# eCog100_ESP8266_Wifi.net
KiCad netlist of a schematic drawn in EAGLE
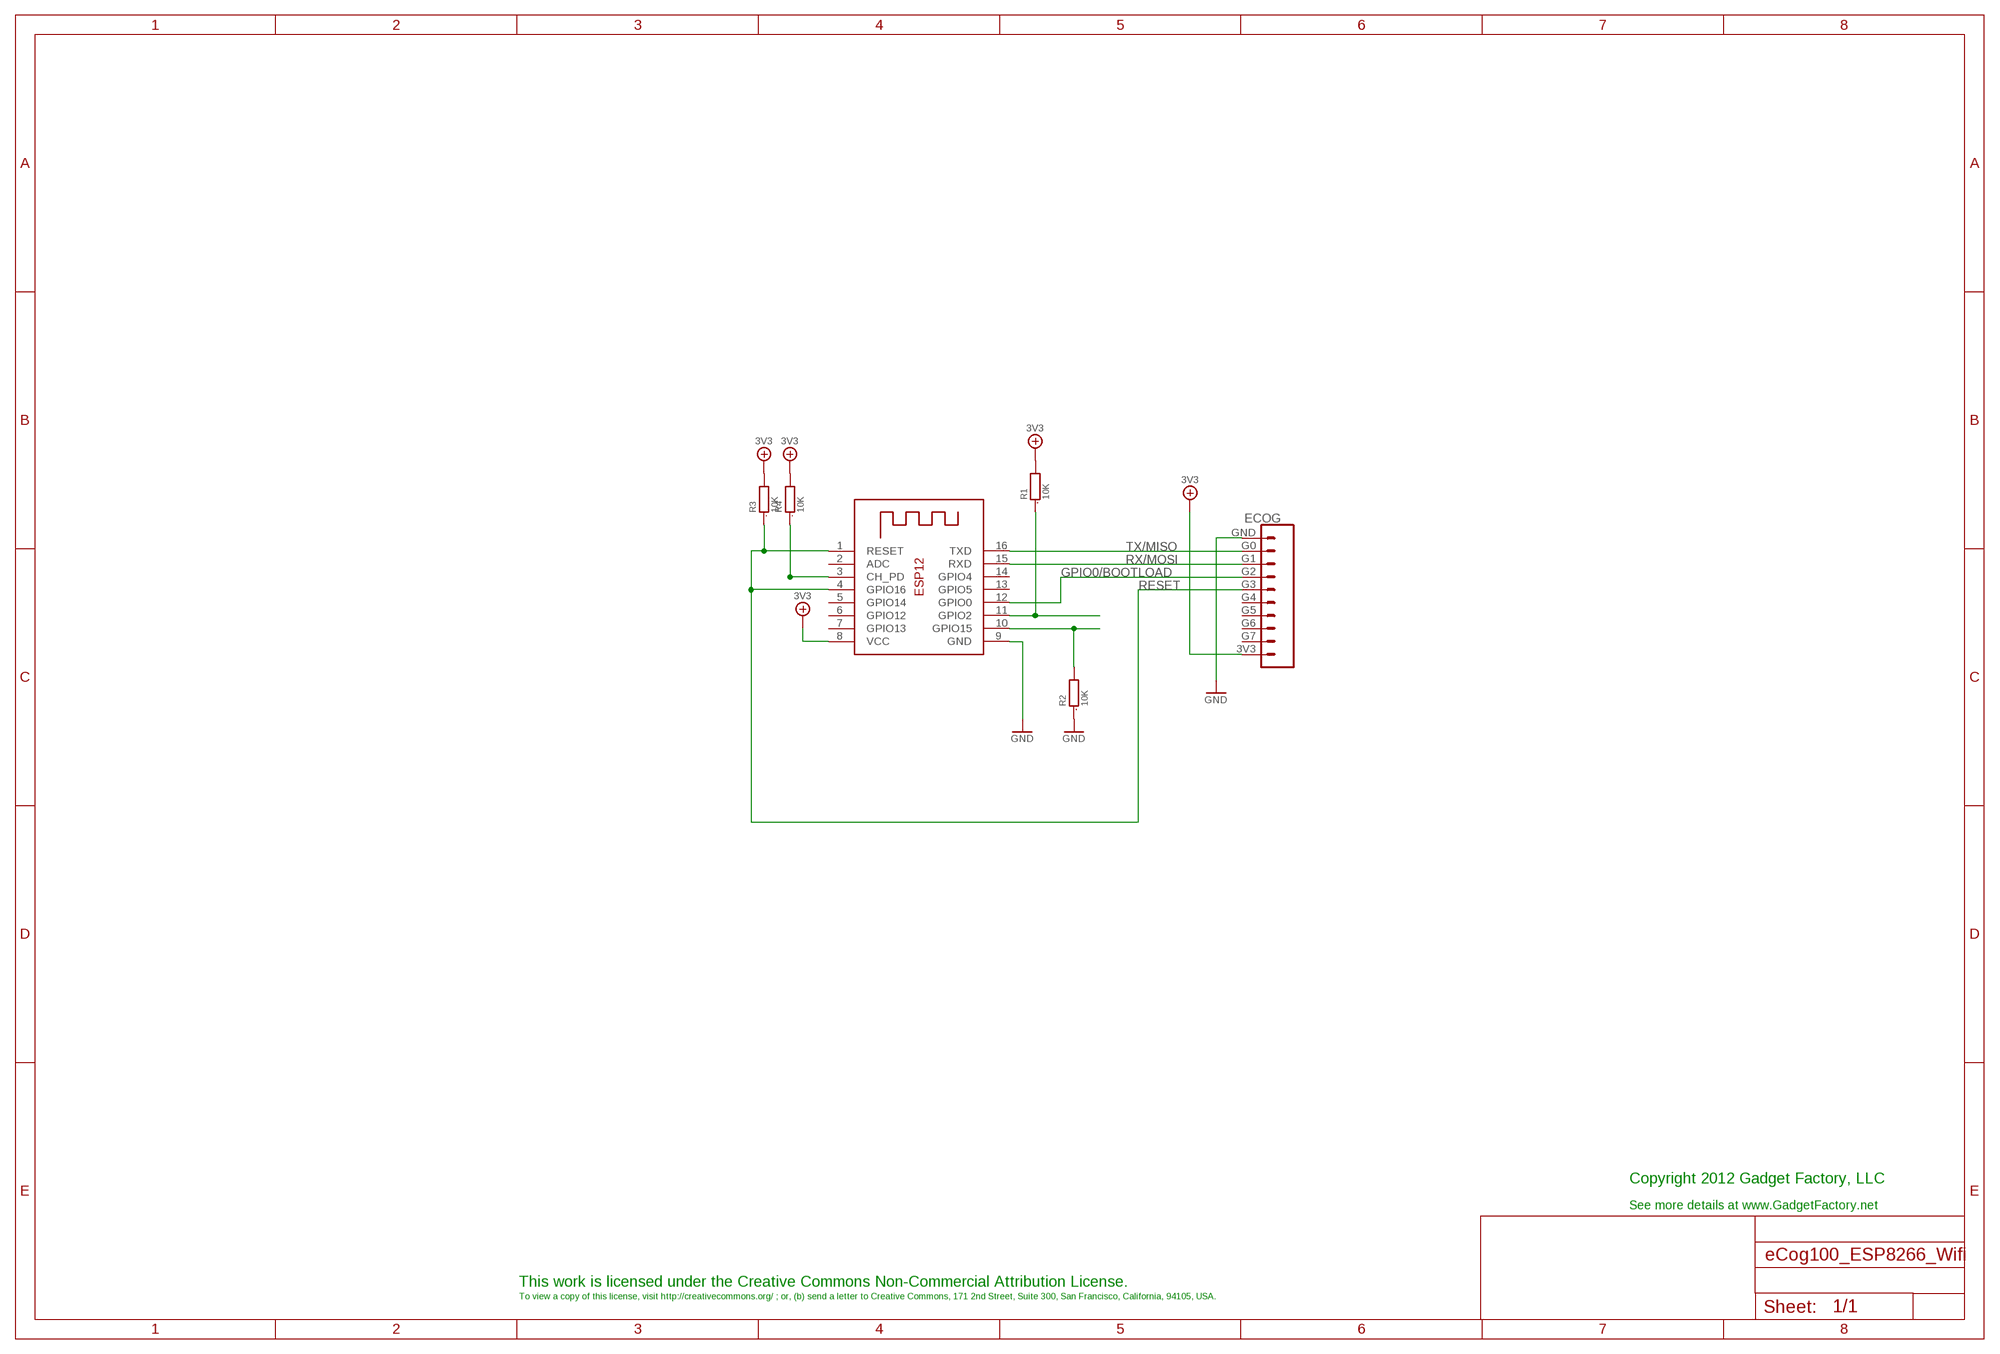
[diagram p0: schematic, sheet 1]

(export (version "E")
  (design (tool "Eeschema 10.0.6"))
  (components
    (comp (ref "ECOG")
      (value "ECOG_GENERAL_ROWSURFACEMOUNT")
      (footprint "eagle-import:ECOG_GENERAL_SMD")
      (libsource (lib "eagle-import") (part "ECOG_GENERAL_ROWSURFACEMOUNT"))
    )
    (comp (ref "R1")
      (value "10K")
      (footprint "eagle-import:0805")
      (libsource (lib "eagle-import") (part "R0805"))
    )
    (comp (ref "R2")
      (value "10K")
      (footprint "eagle-import:0805")
      (libsource (lib "eagle-import") (part "R0805"))
    )
    (comp (ref "R3")
      (value "10K")
      (footprint "eagle-import:0805")
      (libsource (lib "eagle-import") (part "R0805"))
    )
    (comp (ref "R4")
      (value "10K")
      (footprint "eagle-import:0805")
      (libsource (lib "eagle-import") (part "R0805"))
    )
    (comp (ref "X1")
      (value "ESP-12")
      (footprint "eagle-import:ESP-12")
      (libsource (lib "eagle-import") (part "ESP-12"))
    )
  )
  (nets
    (net (code "1") (name "/GPIO0{slash}BOOTLOAD") (class "Default")
      (node (ref "ECOG") (pin "G2") (pinfunction "G2_G2") (pintype "passive"))
      (node (ref "X1") (pin "12") (pinfunction "GPIO0_12") (pintype "bidirectional"))
    )
    (net (code "2") (name "/RESET") (class "Default")
      (node (ref "ECOG") (pin "G3") (pinfunction "G3_G3") (pintype "passive"))
      (node (ref "R3") (pin "1") (pinfunction "1_1") (pintype "passive"))
      (node (ref "X1") (pin "1") (pinfunction "RESET_1") (pintype "input"))
      (node (ref "X1") (pin "4") (pinfunction "GPIO16_4") (pintype "bidirectional"))
    )
    (net (code "3") (name "/RX{slash}MOSI") (class "Default")
      (node (ref "ECOG") (pin "G1") (pinfunction "G1_G1") (pintype "passive"))
      (node (ref "X1") (pin "15") (pinfunction "RXD_15") (pintype "input"))
    )
    (net (code "4") (name "/TX{slash}MISO") (class "Default")
      (node (ref "ECOG") (pin "G0") (pinfunction "G0_G0") (pintype "passive"))
      (node (ref "X1") (pin "16") (pinfunction "TXD_16") (pintype "output"))
    )
    (net (code "5") (name "3V3") (class "Default")
      (node (ref "ECOG") (pin "3V3") (pinfunction "3V3_3V3") (pintype "power_in"))
      (node (ref "R1") (pin "2") (pinfunction "2_2") (pintype "passive"))
      (node (ref "R3") (pin "2") (pinfunction "2_2") (pintype "passive"))
      (node (ref "R4") (pin "2") (pinfunction "2_2") (pintype "passive"))
      (node (ref "X1") (pin "8") (pinfunction "VCC_8") (pintype "power_in"))
    )
    (net (code "6") (name "GND") (class "Default")
      (node (ref "ECOG") (pin "GND") (pinfunction "GND_GND") (pintype "power_in"))
      (node (ref "R2") (pin "1") (pinfunction "1_1") (pintype "passive"))
      (node (ref "X1") (pin "9") (pinfunction "GND_9") (pintype "power_in"))
    )
    (net (code "7") (name "Net-(X1-CH_PD)") (class "Default")
      (node (ref "R4") (pin "1") (pinfunction "1_1") (pintype "passive"))
      (node (ref "X1") (pin "3") (pinfunction "CH_PD_3") (pintype "input"))
    )
    (net (code "8") (name "Net-(X1-GPIO2)") (class "Default")
      (node (ref "R1") (pin "1") (pinfunction "1_1") (pintype "passive"))
      (node (ref "X1") (pin "11") (pinfunction "GPIO2_11") (pintype "bidirectional"))
    )
    (net (code "9") (name "Net-(X1-GPIO15)") (class "Default")
      (node (ref "R2") (pin "2") (pinfunction "2_2") (pintype "passive"))
      (node (ref "X1") (pin "10") (pinfunction "GPIO15_10") (pintype "bidirectional"))
    )
    (net (code "10") (name "unconnected-(ECOG-PadG4)") (class "Default")
      (node (ref "ECOG") (pin "G4") (pinfunction "G4_G4") (pintype "passive"))
    )
    (net (code "11") (name "unconnected-(ECOG-PadG5)") (class "Default")
      (node (ref "ECOG") (pin "G5") (pinfunction "G5_G5") (pintype "passive"))
    )
    (net (code "12") (name "unconnected-(ECOG-PadG6)") (class "Default")
      (node (ref "ECOG") (pin "G6") (pinfunction "G6_G6") (pintype "passive"))
    )
    (net (code "13") (name "unconnected-(ECOG-PadG7)") (class "Default")
      (node (ref "ECOG") (pin "G7") (pinfunction "G7_G7") (pintype "passive"))
    )
    (net (code "14") (name "unconnected-(X1-ADC-Pad2)") (class "Default")
      (node (ref "X1") (pin "2") (pinfunction "ADC_2") (pintype "passive"))
    )
    (net (code "15") (name "unconnected-(X1-GPIO4-Pad14)") (class "Default")
      (node (ref "X1") (pin "14") (pinfunction "GPIO4_14") (pintype "bidirectional"))
    )
    (net (code "16") (name "unconnected-(X1-GPIO5-Pad13)") (class "Default")
      (node (ref "X1") (pin "13") (pinfunction "GPIO5_13") (pintype "bidirectional"))
    )
    (net (code "17") (name "unconnected-(X1-GPIO12-Pad6)") (class "Default")
      (node (ref "X1") (pin "6") (pinfunction "GPIO12_6") (pintype "bidirectional"))
    )
    (net (code "18") (name "unconnected-(X1-GPIO13-Pad7)") (class "Default")
      (node (ref "X1") (pin "7") (pinfunction "GPIO13_7") (pintype "bidirectional"))
    )
    (net (code "19") (name "unconnected-(X1-GPIO14-Pad5)") (class "Default")
      (node (ref "X1") (pin "5") (pinfunction "GPIO14_5") (pintype "bidirectional"))
    )
  )
)
